# User_Interface.net
KiCad netlist of a schematic drawn in Altium Designer
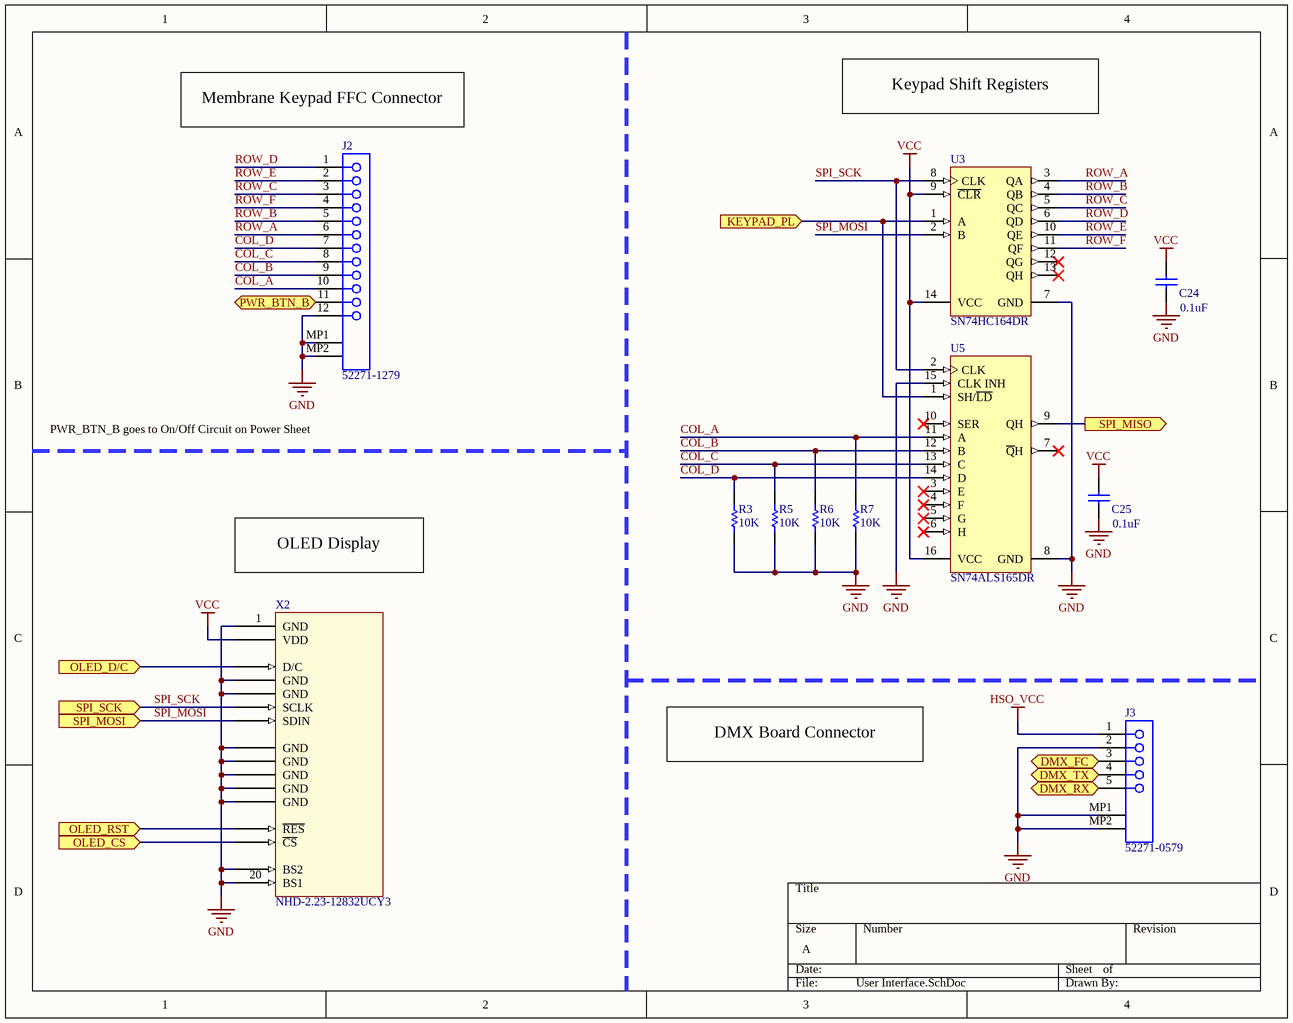
[diagram p0: User Interface.SchDoc]

(export (version "E")
  (design (tool "Eeschema 10.0.6"))
  (components
    (comp (ref "C24")
      (value "0.1uF")
      (footprint "CAPC0603(1608)100_L")
      (description "CAP 27pF 16V ±0.5pF 0603 (1608 Metric) Thickness 1mm SMD")
      (fields (field (name "TOLERANCE") "Â±0.5pF"))
      (libsource (lib "Altium Content Vault") (part "CMP-1035-00873-1"))
    )
    (comp (ref "C25")
      (value "0.1uF")
      (footprint "CAPC0603(1608)100_L")
      (description "CAP 27pF 16V ±0.5pF 0603 (1608 Metric) Thickness 1mm SMD")
      (fields (field (name "TOLERANCE") "Â±0.5pF"))
      (libsource (lib "Altium Content Vault") (part "CMP-1035-00873-1"))
    )
    (comp (ref "J2")
      (value "52271-1279")
      (footprint "MOLX-52271-1279")
      (fields (field (name "MANUFACTURER") "Molex"))
      (libsource (lib "Molex FFC - FPC Connectors (SMT)") (part "52271-1279"))
    )
    (comp (ref "J3")
      (value "52271-0579")
      (footprint "MOLX-52271-0579")
      (fields (field (name "MANUFACTURER") "Molex"))
      (libsource (lib "Molex FFC - FPC Connectors (SMT)") (part "52271-0579"))
    )
    (comp (ref "R3")
      (value "10K")
      (footprint "RESC0603(1608)_N")
      (description "Jumper 0603 (1608 Metric)")
      (fields (field (name "POWER") "None"))
      (libsource (lib "Altium Content Vault") (part "CMP-1012-00001-1"))
    )
    (comp (ref "R5")
      (value "10K")
      (footprint "RESC0603(1608)_N")
      (description "Jumper 0603 (1608 Metric)")
      (fields (field (name "POWER") "None"))
      (libsource (lib "Altium Content Vault") (part "CMP-1012-00001-1"))
    )
    (comp (ref "R6")
      (value "10K")
      (footprint "RESC0603(1608)_N")
      (description "Jumper 0603 (1608 Metric)")
      (fields (field (name "POWER") "None"))
      (libsource (lib "Altium Content Vault") (part "CMP-1012-00001-1"))
    )
    (comp (ref "R7")
      (value "10K")
      (footprint "RESC0603(1608)_N")
      (description "Jumper 0603 (1608 Metric)")
      (fields (field (name "POWER") "None"))
      (libsource (lib "Altium Content Vault") (part "CMP-1012-00001-1"))
    )
    (comp (ref "U3")
      (value "SN74HC164DR")
      (footprint "D0014A_M")
      (description "8-Bit Parallel-Out Serial Shift Registers, D0014A, LARGE T&R")
      (fields
        (field (name "MANUFACTURER") "Texas Instruments")
        (field (name "GENERIC PART NUMBER") "SN74HC164")
      )
      (libsource (lib "Altium Content Vault") (part "TI-SNX4XXX164X-14"))
    )
    (comp (ref "U5")
      (value "SN74ALS165DR")
      (footprint "D0016A_L")
      (description "Parallel-Load 8-Bit Serial Shift Registers, D0016A, LARGE T&R")
      (fields
        (field (name "GENERIC PART NUMBER") "SN74ALS165")
        (field (name "MANUFACTURER") "Texas Instruments")
      )
      (libsource (lib "Altium Content Vault") (part "CMP-0780-00014-3"))
    )
    (comp (ref "X2")
      (value "NHD-2.23-12832UCY3")
      (footprint "NHD-2.23-12832UCY3")
      (libsource (lib "Newhaven Display") (part "NHD-2.23-12832UCY3"))
    )
  )
  (nets
    (net (code "1") (name "/COL_A") (class "Default")
      (node (ref "J2") (pin "10") (pinfunction "10_10") (pintype "passive"))
      (node (ref "R7") (pin "2") (pinfunction "2_2") (pintype "passive"))
      (node (ref "U5") (pin "11") (pinfunction "A_11") (pintype "input"))
    )
    (net (code "2") (name "/COL_B") (class "Default")
      (node (ref "J2") (pin "9") (pinfunction "9_9") (pintype "passive"))
      (node (ref "R6") (pin "2") (pinfunction "2_2") (pintype "passive"))
      (node (ref "U5") (pin "12") (pinfunction "B_12") (pintype "input"))
    )
    (net (code "3") (name "/COL_C") (class "Default")
      (node (ref "J2") (pin "8") (pinfunction "8_8") (pintype "passive"))
      (node (ref "R5") (pin "2") (pinfunction "2_2") (pintype "passive"))
      (node (ref "U5") (pin "13") (pinfunction "C_13") (pintype "input"))
    )
    (net (code "4") (name "/COL_D") (class "Default")
      (node (ref "J2") (pin "7") (pinfunction "7_7") (pintype "passive"))
      (node (ref "R3") (pin "2") (pinfunction "2_2") (pintype "passive"))
      (node (ref "U5") (pin "14") (pinfunction "D_14") (pintype "input"))
    )
    (net (code "5") (name "/DMX_FC") (class "Default")
      (node (ref "J3") (pin "3") (pinfunction "3_3") (pintype "passive"))
    )
    (net (code "6") (name "/DMX_RX") (class "Default")
      (node (ref "J3") (pin "5") (pinfunction "5_5") (pintype "passive"))
    )
    (net (code "7") (name "/DMX_TX") (class "Default")
      (node (ref "J3") (pin "4") (pinfunction "4_4") (pintype "passive"))
    )
    (net (code "8") (name "/KEYPAD_PL") (class "Default")
      (node (ref "U3") (pin "1") (pinfunction "A_1") (pintype "input"))
      (node (ref "U5") (pin "1") (pinfunction "SH/~{LD}_1") (pintype "input"))
    )
    (net (code "9") (name "/OLED_CS") (class "Default")
      (node (ref "X2") (pin "17") (pinfunction "~{CS}_17") (pintype "input"))
    )
    (net (code "10") (name "/OLED_D{slash}C") (class "Default")
      (node (ref "X2") (pin "4") (pinfunction "D/C_4") (pintype "input"))
    )
    (net (code "11") (name "/OLED_RST") (class "Default")
      (node (ref "X2") (pin "16") (pinfunction "~{RES}_16") (pintype "input"))
    )
    (net (code "12") (name "/PWR_BTN_B") (class "Default")
      (node (ref "J2") (pin "11") (pinfunction "11_11") (pintype "passive"))
    )
    (net (code "13") (name "/ROW_A") (class "Default")
      (node (ref "J2") (pin "6") (pinfunction "6_6") (pintype "passive"))
      (node (ref "U3") (pin "3") (pinfunction "QA_3") (pintype "output"))
    )
    (net (code "14") (name "/ROW_B") (class "Default")
      (node (ref "J2") (pin "5") (pinfunction "5_5") (pintype "passive"))
      (node (ref "U3") (pin "4") (pinfunction "QB_4") (pintype "output"))
    )
    (net (code "15") (name "/ROW_C") (class "Default")
      (node (ref "J2") (pin "3") (pinfunction "3_3") (pintype "passive"))
      (node (ref "U3") (pin "5") (pinfunction "QC_5") (pintype "output"))
    )
    (net (code "16") (name "/ROW_D") (class "Default")
      (node (ref "J2") (pin "1") (pinfunction "1_1") (pintype "passive"))
      (node (ref "U3") (pin "6") (pinfunction "QD_6") (pintype "output"))
    )
    (net (code "17") (name "/ROW_E") (class "Default")
      (node (ref "J2") (pin "2") (pinfunction "2_2") (pintype "passive"))
      (node (ref "U3") (pin "10") (pinfunction "QE_10") (pintype "output"))
    )
    (net (code "18") (name "/ROW_F") (class "Default")
      (node (ref "J2") (pin "4") (pinfunction "4_4") (pintype "passive"))
      (node (ref "U3") (pin "11") (pinfunction "QF_11") (pintype "output"))
    )
    (net (code "19") (name "/SPI_MISO") (class "Default")
      (node (ref "U5") (pin "9") (pinfunction "QH_9") (pintype "output"))
    )
    (net (code "20") (name "/SPI_MOSI") (class "Default")
      (node (ref "U3") (pin "2") (pinfunction "B_2") (pintype "input"))
      (node (ref "X2") (pin "8") (pinfunction "SDIN_8") (pintype "input"))
    )
    (net (code "21") (name "/SPI_SCK") (class "Default")
      (node (ref "U3") (pin "8") (pinfunction "CLK_8") (pintype "input"))
      (node (ref "U5") (pin "2") (pinfunction "CLK_2") (pintype "input"))
      (node (ref "X2") (pin "7") (pinfunction "SCLK_7") (pintype "input"))
    )
    (net (code "22") (name "GND") (class "Default")
      (node (ref "C24") (pin "1") (pinfunction "1_1") (pintype "passive"))
      (node (ref "C25") (pin "1") (pinfunction "1_1") (pintype "passive"))
      (node (ref "J2") (pin "12") (pinfunction "12_12") (pintype "passive"))
      (node (ref "J2") (pin "MP1") (pinfunction "MP1_MP1") (pintype "passive"))
      (node (ref "J2") (pin "MP2") (pinfunction "MP2_MP2") (pintype "passive"))
      (node (ref "J3") (pin "2") (pinfunction "2_2") (pintype "passive"))
      (node (ref "J3") (pin "MP1") (pinfunction "MP1_MP1") (pintype "passive"))
      (node (ref "J3") (pin "MP2") (pinfunction "MP2_MP2") (pintype "passive"))
      (node (ref "R3") (pin "1") (pinfunction "1_1") (pintype "passive"))
      (node (ref "R5") (pin "1") (pinfunction "1_1") (pintype "passive"))
      (node (ref "R6") (pin "1") (pinfunction "1_1") (pintype "passive"))
      (node (ref "R7") (pin "1") (pinfunction "1_1") (pintype "passive"))
      (node (ref "U3") (pin "7") (pinfunction "GND_7") (pintype "power_in"))
      (node (ref "U5") (pin "15") (pinfunction "CLK_INH_15") (pintype "input"))
      (node (ref "U5") (pin "8") (pinfunction "GND_8") (pintype "power_in"))
      (node (ref "X2") (pin "1") (pinfunction "GND_1") (pintype "power_in"))
      (node (ref "X2") (pin "10") (pinfunction "GND_10") (pintype "power_in"))
      (node (ref "X2") (pin "11") (pinfunction "GND_11") (pintype "power_in"))
      (node (ref "X2") (pin "12") (pinfunction "GND_12") (pintype "power_in"))
      (node (ref "X2") (pin "13") (pinfunction "GND_13") (pintype "power_in"))
      (node (ref "X2") (pin "14") (pinfunction "GND_14") (pintype "power_in"))
      (node (ref "X2") (pin "19") (pinfunction "BS2_19") (pintype "input"))
      (node (ref "X2") (pin "20") (pinfunction "BS1_20") (pintype "input"))
      (node (ref "X2") (pin "5") (pinfunction "GND_5") (pintype "power_in"))
      (node (ref "X2") (pin "6") (pinfunction "GND_6") (pintype "power_in"))
    )
    (net (code "23") (name "HSO_VCC") (class "Default")
      (node (ref "J3") (pin "1") (pinfunction "1_1") (pintype "passive"))
    )
    (net (code "24") (name "VCC") (class "Default")
      (node (ref "C24") (pin "2") (pinfunction "2_2") (pintype "passive"))
      (node (ref "C25") (pin "2") (pinfunction "2_2") (pintype "passive"))
      (node (ref "U3") (pin "14") (pinfunction "VCC_14") (pintype "power_in"))
      (node (ref "U3") (pin "9") (pinfunction "~{CLR}_9") (pintype "input"))
      (node (ref "U5") (pin "16") (pinfunction "VCC_16") (pintype "power_in"))
      (node (ref "X2") (pin "2") (pinfunction "VDD_2") (pintype "power_in"))
    )
    (net (code "25") (name "unconnected-(U3-QG-Pad12)") (class "Default")
      (node (ref "U3") (pin "12") (pinfunction "QG_12") (pintype "output+no_connect"))
    )
    (net (code "26") (name "unconnected-(U3-QH-Pad13)") (class "Default")
      (node (ref "U3") (pin "13") (pinfunction "QH_13") (pintype "output+no_connect"))
    )
    (net (code "27") (name "unconnected-(U5-E-Pad3)") (class "Default")
      (node (ref "U5") (pin "3") (pinfunction "E_3") (pintype "input+no_connect"))
    )
    (net (code "28") (name "unconnected-(U5-F-Pad4)") (class "Default")
      (node (ref "U5") (pin "4") (pinfunction "F_4") (pintype "input+no_connect"))
    )
    (net (code "29") (name "unconnected-(U5-G-Pad5)") (class "Default")
      (node (ref "U5") (pin "5") (pinfunction "G_5") (pintype "input+no_connect"))
    )
    (net (code "30") (name "unconnected-(U5-H-Pad6)") (class "Default")
      (node (ref "U5") (pin "6") (pinfunction "H_6") (pintype "input+no_connect"))
    )
    (net (code "31") (name "unconnected-(U5-SER-Pad10)") (class "Default")
      (node (ref "U5") (pin "10") (pinfunction "SER_10") (pintype "input+no_connect"))
    )
    (net (code "32") (name "unconnected-(U5-~{Q}H-Pad7)") (class "Default")
      (node (ref "U5") (pin "7") (pinfunction "~{Q}H_7") (pintype "output+no_connect"))
    )
    (net (code "33") (name "unconnected-(X2-NC-Pad3)") (class "Default")
      (node (ref "X2") (pin "3") (pinfunction "NC_3") (pintype "passive"))
    )
    (net (code "34") (name "unconnected-(X2-NC-Pad9)") (class "Default")
      (node (ref "X2") (pin "9") (pinfunction "NC_9") (pintype "passive"))
    )
    (net (code "35") (name "unconnected-(X2-NC-Pad15)") (class "Default")
      (node (ref "X2") (pin "15") (pinfunction "NC_15") (pintype "passive"))
    )
    (net (code "36") (name "unconnected-(X2-NC-Pad18)") (class "Default")
      (node (ref "X2") (pin "18") (pinfunction "NC_18") (pintype "passive"))
    )
  )
)
